# SCH.net
KiCad netlist of a schematic drawn in EasyEDA
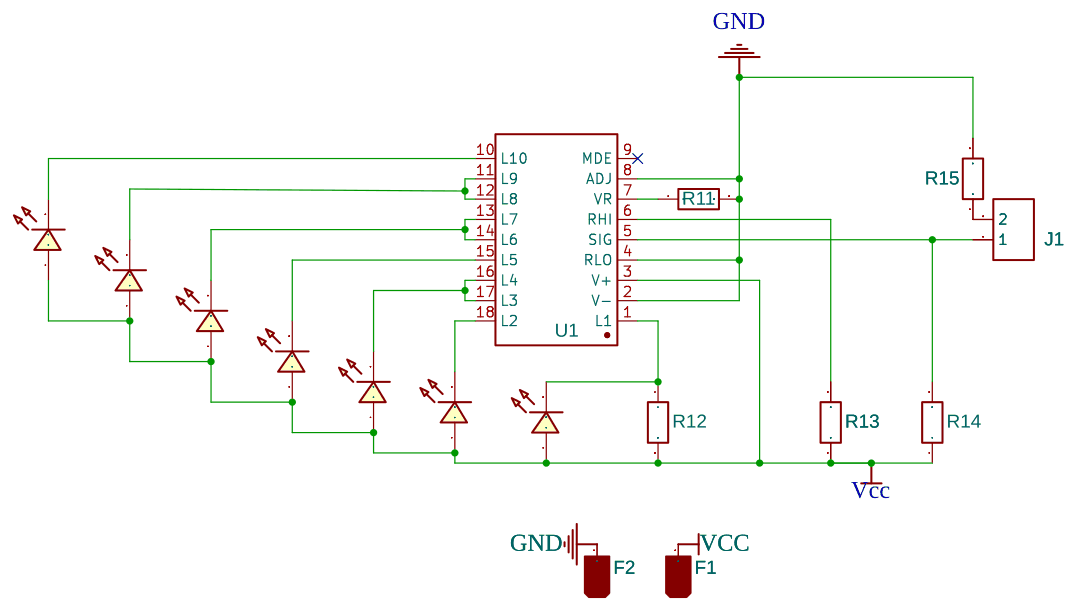
[diagram p0: schematic sheet]

(export (version "E")
  (design (tool "Eeschema 10.0.6"))
  (components
    (comp (ref "F1")
      (value "FASTON-PCB-6.3X0.8")
      (fields
        (field (name "Manufacturer Part") "63849-1")
        (field (name "Manufacturer") "AMP - TE CONNECTIVITY")
      )
      (libsource (lib "") (part "FASTON-PCB-6.3X0.8"))
    )
    (comp (ref "F2")
      (value "FASTON-PCB-6.3X0.8")
      (fields
        (field (name "Manufacturer Part") "63849-1")
        (field (name "Manufacturer") "AMP - TE CONNECTIVITY")
      )
      (libsource (lib "") (part "FASTON-PCB-6.3X0.8"))
    )
    (comp (ref "J1") (value "HDR-M-2.54_1x2") (libsource (lib "") (part "HDR-M-2.54_1x2")))
    (comp (ref "LED11")
      (value "LED-TH-5mm_R")
      (fields
        (field (name "Manufacturer Part") "333-2SURD/S530-A3")
        (field (name "Manufacturer") "EVERLIGHT(台湾亿光)")
      )
      (libsource (lib "") (part "LED-TH-5mm_R"))
    )
    (comp (ref "LED12")
      (value "LED-TH-3mm_R")
      (fields
        (field (name "Manufacturer Part") "204-10SDRD/S530-A3-L")
        (field (name "Manufacturer") "EVERLIGHT(台湾亿光)")
      )
      (libsource (lib "") (part "LED-TH-3mm_R"))
    )
    (comp (ref "LED13")
      (value "LED-TH-3mm_G")
      (fields
        (field (name "Manufacturer Part") "204-10SYGD/S530-E3")
        (field (name "Manufacturer") "EVERLIGHT(台湾亿光)")
      )
      (libsource (lib "") (part "LED-TH-3mm_G"))
    )
    (comp (ref "LED14")
      (value "LED-TH-3mm_G")
      (fields
        (field (name "Manufacturer Part") "204-10SYGD/S530-E3")
        (field (name "Manufacturer") "EVERLIGHT(台湾亿光)")
      )
      (libsource (lib "") (part "LED-TH-3mm_G"))
    )
    (comp (ref "LED15")
      (value "LED-TH-3mm_G")
      (fields
        (field (name "Manufacturer Part") "204-10SYGD/S530-E3")
        (field (name "Manufacturer") "EVERLIGHT(台湾亿光)")
      )
      (libsource (lib "") (part "LED-TH-3mm_G"))
    )
    (comp (ref "LED16")
      (value "LED-TH-3mm_G")
      (fields
        (field (name "Manufacturer Part") "204-10SYGD/S530-E3")
        (field (name "Manufacturer") "EVERLIGHT(台湾亿光)")
      )
      (libsource (lib "") (part "LED-TH-3mm_G"))
    )
    (comp (ref "LED17")
      (value "LED-TH-3mm_G")
      (fields
        (field (name "Manufacturer Part") "204-10SYGD/S530-E3")
        (field (name "Manufacturer") "EVERLIGHT(台湾亿光)")
      )
      (libsource (lib "") (part "LED-TH-3mm_G"))
    )
    (comp (ref "R11") (value "1K") (libsource (lib "") (part "R_AXIAL-0.4_EU_1")))
    (comp (ref "R12") (value "4k7") (libsource (lib "") (part "R_AXIAL-0.4_EU_2")))
    (comp (ref "R13") (value "33k") (libsource (lib "") (part "R_AXIAL-0.4_EU")))
    (comp (ref "R14") (value "680") (libsource (lib "") (part "R_AXIAL-0.3_EU")))
    (comp (ref "R15") (value "15") (libsource (lib "") (part "R_AXIAL-0.3_EU")))
    (comp (ref "U1")
      (value "LM3914N-1/NOPB")
      (fields (field (name "Manufacturer") "TI"))
      (libsource (lib "") (part "LM3914N-1/NOPB"))
    )
  )
  (nets
    (net (code "1") (name "GND") (class "Default")
      (node (ref "F2") (pin "1") (pinfunction "1_1") (pintype "unspecified"))
      (node (ref "R11") (pin "2") (pinfunction "2_2") (pintype "unspecified"))
      (node (ref "R15") (pin "2") (pinfunction "2_2") (pintype "unspecified"))
      (node (ref "U1") (pin "2") (pinfunction "V-_2") (pintype "unspecified"))
      (node (ref "U1") (pin "4") (pinfunction "RLO_4") (pintype "unspecified"))
      (node (ref "U1") (pin "8") (pinfunction "ADJ_8") (pintype "unspecified"))
    )
    (net (code "2") (name "Net-(J1-Pad2)") (class "Default")
      (node (ref "J1") (pin "2") (pinfunction "2_2") (pintype "unspecified"))
      (node (ref "R15") (pin "1") (pinfunction "1_1") (pintype "unspecified"))
    )
    (net (code "3") (name "Net-(U1-L1)") (class "Default")
      (node (ref "LED11") (pin "2") (pinfunction "2_2") (pintype "unspecified"))
      (node (ref "R12") (pin "1") (pinfunction "1_1") (pintype "unspecified"))
      (node (ref "U1") (pin "1") (pinfunction "L1_1") (pintype "unspecified"))
    )
    (net (code "4") (name "Net-(U1-L2)") (class "Default")
      (node (ref "LED12") (pin "2") (pinfunction "2_2") (pintype "unspecified"))
      (node (ref "U1") (pin "18") (pinfunction "L2_18") (pintype "unspecified"))
    )
    (net (code "5") (name "Net-(U1-L3)") (class "Default")
      (node (ref "LED13") (pin "2") (pinfunction "2_2") (pintype "unspecified"))
      (node (ref "U1") (pin "16") (pinfunction "L4_16") (pintype "unspecified"))
      (node (ref "U1") (pin "17") (pinfunction "L3_17") (pintype "unspecified"))
    )
    (net (code "6") (name "Net-(U1-L5)") (class "Default")
      (node (ref "LED14") (pin "2") (pinfunction "2_2") (pintype "unspecified"))
      (node (ref "U1") (pin "15") (pinfunction "L5_15") (pintype "unspecified"))
    )
    (net (code "7") (name "Net-(U1-L6)") (class "Default")
      (node (ref "LED15") (pin "2") (pinfunction "2_2") (pintype "unspecified"))
      (node (ref "U1") (pin "13") (pinfunction "L7_13") (pintype "unspecified"))
      (node (ref "U1") (pin "14") (pinfunction "L6_14") (pintype "unspecified"))
    )
    (net (code "8") (name "Net-(U1-L8)") (class "Default")
      (node (ref "LED16") (pin "2") (pinfunction "2_2") (pintype "unspecified"))
      (node (ref "U1") (pin "11") (pinfunction "L9_11") (pintype "unspecified"))
      (node (ref "U1") (pin "12") (pinfunction "L8_12") (pintype "unspecified"))
    )
    (net (code "9") (name "Net-(U1-L10)") (class "Default")
      (node (ref "LED17") (pin "2") (pinfunction "2_2") (pintype "unspecified"))
      (node (ref "U1") (pin "10") (pinfunction "L10_10") (pintype "unspecified"))
    )
    (net (code "10") (name "Net-(U1-RHI)") (class "Default")
      (node (ref "R13") (pin "2") (pinfunction "2_2") (pintype "unspecified"))
      (node (ref "U1") (pin "6") (pinfunction "RHI_6") (pintype "unspecified"))
    )
    (net (code "11") (name "Net-(U1-SIG)") (class "Default")
      (node (ref "J1") (pin "1") (pinfunction "1_1") (pintype "unspecified"))
      (node (ref "R14") (pin "2") (pinfunction "2_2") (pintype "unspecified"))
      (node (ref "U1") (pin "5") (pinfunction "SIG_5") (pintype "unspecified"))
    )
    (net (code "12") (name "Net-(U1-VR)") (class "Default")
      (node (ref "R11") (pin "1") (pinfunction "1_1") (pintype "unspecified"))
      (node (ref "U1") (pin "7") (pinfunction "VR_7") (pintype "unspecified"))
    )
    (net (code "13") (name "VCC") (class "Default")
      (node (ref "F1") (pin "1") (pinfunction "1_1") (pintype "unspecified"))
    )
    (net (code "14") (name "Vcc") (class "Default")
      (node (ref "LED11") (pin "1") (pinfunction "1_1") (pintype "unspecified"))
      (node (ref "LED12") (pin "1") (pinfunction "1_1") (pintype "unspecified"))
      (node (ref "LED13") (pin "1") (pinfunction "1_1") (pintype "unspecified"))
      (node (ref "LED14") (pin "1") (pinfunction "1_1") (pintype "unspecified"))
      (node (ref "LED15") (pin "1") (pinfunction "1_1") (pintype "unspecified"))
      (node (ref "LED16") (pin "1") (pinfunction "1_1") (pintype "unspecified"))
      (node (ref "LED17") (pin "1") (pinfunction "1_1") (pintype "unspecified"))
      (node (ref "R12") (pin "2") (pinfunction "2_2") (pintype "unspecified"))
      (node (ref "R13") (pin "1") (pinfunction "1_1") (pintype "unspecified"))
      (node (ref "R14") (pin "1") (pinfunction "1_1") (pintype "unspecified"))
      (node (ref "U1") (pin "3") (pinfunction "V+_3") (pintype "unspecified"))
    )
    (net (code "15") (name "unconnected-(U1-MDE-Pad9)") (class "Default")
      (node (ref "U1") (pin "9") (pinfunction "MDE_9") (pintype "unspecified+no_connect"))
    )
  )
)
